# RoverEncoder.net
KiCad netlist of a schematic drawn in EAGLE
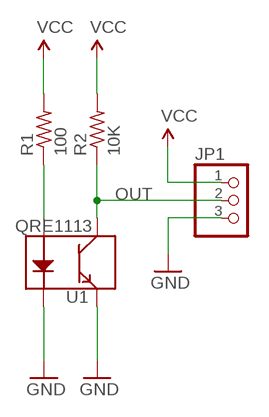
[diagram p0: schematic, sheet 1]

(export (version "E")
  (design (tool "Eeschema 10.0.6"))
  (components
    (comp (ref "JP1")
      (value "PINHD-1X03_2.54-S")
      (footprint "eagle-import:1X03-S")
      (libsource (lib "eagle-import") (part "PINHD-1X03_2.54-S"))
    )
    (comp (ref "R1")
      (value "100")
      (footprint "eagle-import:R0603")
      (libsource (lib "eagle-import") (part "R-US_R0603"))
    )
    (comp (ref "R2")
      (value "10K")
      (footprint "eagle-import:R0603")
      (libsource (lib "eagle-import") (part "R-US_R0603"))
    )
    (comp (ref "U1")
      (value "QRE1113")
      (footprint "eagle-import:QRE1113")
      (libsource (lib "eagle-import") (part "QRE1113"))
    )
  )
  (nets
    (net (code "1") (name "/OUT") (class "Default")
      (node (ref "JP1") (pin "2") (pinfunction "2_2") (pintype "passive"))
      (node (ref "R2") (pin "1") (pinfunction "1_1") (pintype "passive"))
      (node (ref "U1") (pin "3") (pinfunction "C_3") (pintype "bidirectional"))
    )
    (net (code "2") (name "GND") (class "Default")
      (node (ref "JP1") (pin "3") (pinfunction "3_3") (pintype "passive"))
      (node (ref "U1") (pin "2") (pinfunction "K_2") (pintype "bidirectional"))
      (node (ref "U1") (pin "4") (pinfunction "E_4") (pintype "bidirectional"))
    )
    (net (code "3") (name "Net-(U1-A)") (class "Default")
      (node (ref "R1") (pin "1") (pinfunction "1_1") (pintype "passive"))
      (node (ref "U1") (pin "1") (pinfunction "A_1") (pintype "bidirectional"))
    )
    (net (code "4") (name "VCC") (class "Default")
      (node (ref "JP1") (pin "1") (pinfunction "1_1") (pintype "passive"))
      (node (ref "R1") (pin "2") (pinfunction "2_2") (pintype "passive"))
      (node (ref "R2") (pin "2") (pinfunction "2_2") (pintype "passive"))
    )
  )
)
